# KeyPad.net
KiCad netlist of a schematic drawn in Altium Designer
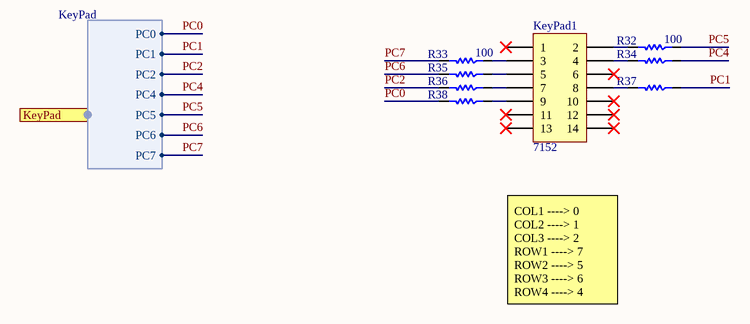
[diagram p0: KeyPad.SchDoc]

(export (version "E")
  (design (tool "Eeschema 10.0.6"))
  (components
    (comp (ref "KeyPad1")
      (value "7x2")
      (footprint "HDR_THT_7x2M_2.54mm")
      (description "Header, dual row, 14 pin")
      (fields (field (name "INFLOW") "7152") (field (name "VALIDATION") "NT"))
      (libsource (lib "aKaReZa") (part "Con_MPH_7x2_V_THT_2.54"))
    )
    (comp (ref "R32")
      (value "100")
      (footprint "RES 1206 (3216X08L)")
      (description "Resistor")
      (fields (field (name "VALIDATION") "Valid"))
      (libsource (lib "aKaReZa") (part "Res_SMD_1206"))
    )
    (comp (ref "R33")
      (value "100")
      (footprint "RES 1206 (3216X08L)")
      (description "Resistor")
      (fields (field (name "VALIDATION") "Valid"))
      (libsource (lib "aKaReZa") (part "Res_SMD_1206"))
    )
    (comp (ref "R34")
      (value "10K")
      (footprint "RES 1206 (3216X08L)")
      (description "Resistor")
      (fields (field (name "VALIDATION") "Valid"))
      (libsource (lib "aKaReZa") (part "Res_SMD_1206"))
    )
    (comp (ref "R35")
      (value "10K")
      (footprint "RES 1206 (3216X08L)")
      (description "Resistor")
      (fields (field (name "VALIDATION") "Valid"))
      (libsource (lib "aKaReZa") (part "Res_SMD_1206"))
    )
    (comp (ref "R36")
      (value "10K")
      (footprint "RES 1206 (3216X08L)")
      (description "Resistor")
      (fields (field (name "VALIDATION") "Valid"))
      (libsource (lib "aKaReZa") (part "Res_SMD_1206"))
    )
    (comp (ref "R37")
      (value "10K")
      (footprint "RES 1206 (3216X08L)")
      (description "Resistor")
      (fields (field (name "VALIDATION") "Valid"))
      (libsource (lib "aKaReZa") (part "Res_SMD_1206"))
    )
    (comp (ref "R38")
      (value "10K")
      (footprint "RES 1206 (3216X08L)")
      (description "Resistor")
      (fields (field (name "VALIDATION") "Valid"))
      (libsource (lib "aKaReZa") (part "Res_SMD_1206"))
    )
  )
  (nets
    (net (code "2") (name "/PC0") (class "Default")
      (node (ref "R38") (pin "2") (pinfunction "2_2") (pintype "passive"))
    )
    (net (code "3") (name "/PC1") (class "Default")
      (node (ref "R37") (pin "1") (pinfunction "1_1") (pintype "passive"))
    )
    (net (code "4") (name "/PC2") (class "Default")
      (node (ref "R36") (pin "2") (pinfunction "2_2") (pintype "passive"))
    )
    (net (code "5") (name "/PC4") (class "Default")
      (node (ref "R34") (pin "1") (pinfunction "1_1") (pintype "passive"))
    )
    (net (code "6") (name "/PC5") (class "Default")
      (node (ref "R32") (pin "1") (pinfunction "1_1") (pintype "passive"))
    )
    (net (code "7") (name "/PC6") (class "Default")
      (node (ref "R35") (pin "2") (pinfunction "2_2") (pintype "passive"))
    )
    (net (code "8") (name "/PC7") (class "Default")
      (node (ref "R33") (pin "2") (pinfunction "2_2") (pintype "passive"))
    )
    (net (code "10") (name "Net-(KeyPad1-Pad2)") (class "Default")
      (node (ref "KeyPad1") (pin "2") (pinfunction "2_2") (pintype "passive"))
      (node (ref "R32") (pin "2") (pinfunction "2_2") (pintype "passive"))
    )
    (net (code "11") (name "Net-(KeyPad1-Pad3)") (class "Default")
      (node (ref "KeyPad1") (pin "3") (pinfunction "3_3") (pintype "passive"))
      (node (ref "R33") (pin "1") (pinfunction "1_1") (pintype "passive"))
    )
    (net (code "12") (name "Net-(KeyPad1-Pad4)") (class "Default")
      (node (ref "KeyPad1") (pin "4") (pinfunction "4_4") (pintype "passive"))
      (node (ref "R34") (pin "2") (pinfunction "2_2") (pintype "passive"))
    )
    (net (code "13") (name "Net-(KeyPad1-Pad5)") (class "Default")
      (node (ref "KeyPad1") (pin "5") (pinfunction "5_5") (pintype "passive"))
      (node (ref "R35") (pin "1") (pinfunction "1_1") (pintype "passive"))
    )
    (net (code "14") (name "Net-(KeyPad1-Pad7)") (class "Default")
      (node (ref "KeyPad1") (pin "7") (pinfunction "7_7") (pintype "passive"))
      (node (ref "R36") (pin "1") (pinfunction "1_1") (pintype "passive"))
    )
    (net (code "15") (name "Net-(KeyPad1-Pad8)") (class "Default")
      (node (ref "KeyPad1") (pin "8") (pinfunction "8_8") (pintype "passive"))
      (node (ref "R37") (pin "2") (pinfunction "2_2") (pintype "passive"))
    )
    (net (code "16") (name "Net-(KeyPad1-Pad9)") (class "Default")
      (node (ref "KeyPad1") (pin "9") (pinfunction "9_9") (pintype "passive"))
      (node (ref "R38") (pin "1") (pinfunction "1_1") (pintype "passive"))
    )
    (net (code "17") (name "unconnected-(KeyPad1-Pad1)") (class "Default")
      (node (ref "KeyPad1") (pin "1") (pinfunction "1_1") (pintype "passive+no_connect"))
    )
    (net (code "18") (name "unconnected-(KeyPad1-Pad6)") (class "Default")
      (node (ref "KeyPad1") (pin "6") (pinfunction "6_6") (pintype "passive+no_connect"))
    )
    (net (code "19") (name "unconnected-(KeyPad1-Pad10)") (class "Default")
      (node (ref "KeyPad1") (pin "10") (pinfunction "10_10") (pintype "passive+no_connect"))
    )
    (net (code "20") (name "unconnected-(KeyPad1-Pad11)") (class "Default")
      (node (ref "KeyPad1") (pin "11") (pinfunction "11_11") (pintype "passive+no_connect"))
    )
    (net (code "21") (name "unconnected-(KeyPad1-Pad12)") (class "Default")
      (node (ref "KeyPad1") (pin "12") (pinfunction "12_12") (pintype "passive+no_connect"))
    )
    (net (code "22") (name "unconnected-(KeyPad1-Pad13)") (class "Default")
      (node (ref "KeyPad1") (pin "13") (pinfunction "13_13") (pintype "passive+no_connect"))
    )
    (net (code "23") (name "unconnected-(KeyPad1-Pad14)") (class "Default")
      (node (ref "KeyPad1") (pin "14") (pinfunction "14_14") (pintype "passive+no_connect"))
    )
  )
)
